# MercurialSDR_PWR.net
KiCad netlist of a schematic drawn in Altium Designer
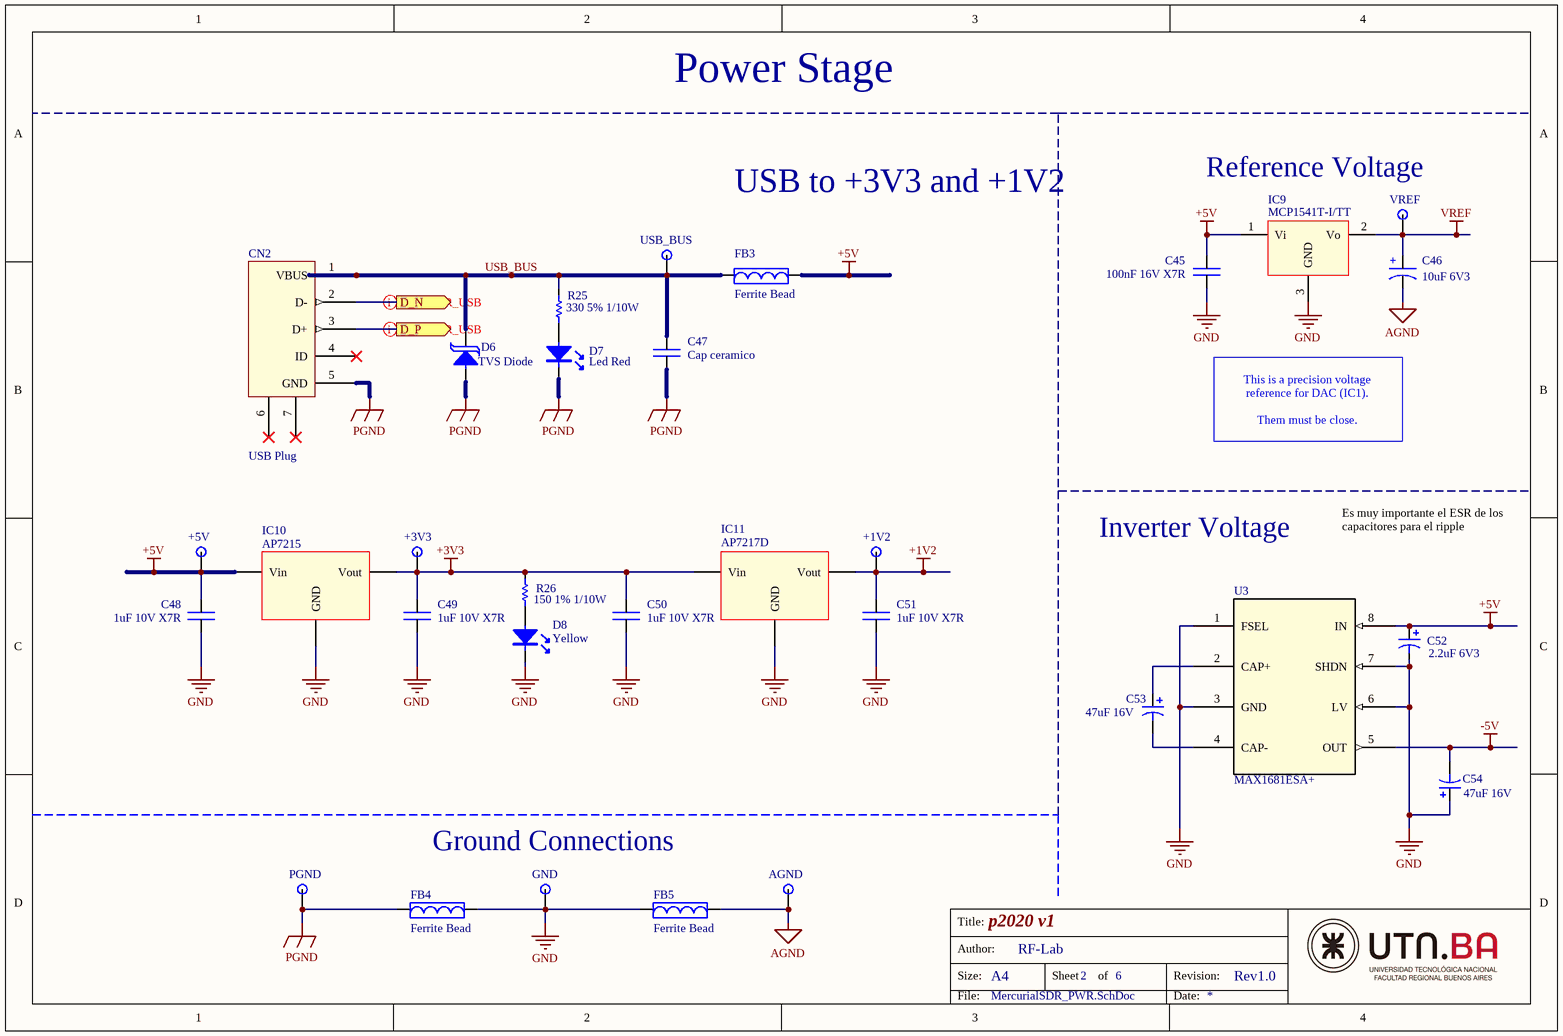
[diagram p0: MercurialSDR_PWR.SchDoc]

(export (version "E")
  (design (tool "Eeschema 10.0.6"))
  (components
    (comp (ref "C45")
      (value "100nF 16V X7R")
      (footprint "CAP_0603")
      (description "Capacitor no polarizado")
      (fields (field (name "Comment") "100nF 16V X7R - CL10B104KO8NNNC"))
      (libsource (lib "MercurialSDR") (part "Cap"))
    )
    (comp (ref "C46")
      (value "10uF 6V3")
      (footprint "CAP_TANT_1206")
      (description "Capacitor polarizado")
      (fields (field (name "Comment") "10uF 6V3 - TAJA106K006RNJ"))
      (libsource (lib "MercurialSDR") (part "Cap Pol"))
    )
    (comp (ref "C47")
      (value "Cap ceramico")
      (footprint "CAP_0603")
      (description "Capacitor no polarizado")
      (fields (field (name "Comment") "10nF 16v X7R  - CC0603KRX7R7BB103"))
      (libsource (lib "MercurialSDR") (part "Cap"))
    )
    (comp (ref "C48")
      (value "1uF 10V X7R")
      (footprint "CAP_0603")
      (description "Capacitor no polarizado")
      (fields (field (name "Comment") "1uF 10V X7R - CL10B105KP8NNNC"))
      (libsource (lib "MercurialSDR") (part "Cap"))
    )
    (comp (ref "C49")
      (value "1uF 10V X7R")
      (footprint "CAP_0603")
      (description "Capacitor no polarizado")
      (fields (field (name "Comment") "1uF 10V X7R - CL10B105KP8NNNC"))
      (libsource (lib "MercurialSDR") (part "Cap"))
    )
    (comp (ref "C50")
      (value "1uF 10V X7R")
      (footprint "CAP_0603")
      (description "Capacitor no polarizado")
      (fields (field (name "Comment") "1uF 10V X7R - CL10B105KP8NNNC"))
      (libsource (lib "MercurialSDR") (part "Cap"))
    )
    (comp (ref "C51")
      (value "1uF 10V X7R")
      (footprint "CAP_0603")
      (description "Capacitor no polarizado")
      (fields (field (name "Comment") "1uF 10V X7R - CL10B105KP8NNNC"))
      (libsource (lib "MercurialSDR") (part "Cap"))
    )
    (comp (ref "C52")
      (value "2.2uF 6V3")
      (footprint "CAP_0603")
      (description "Capacitor Polarizado")
      (fields
        (field (name "Comment") "2.2uF 6V3 -  TMCJ1A225MTRF")
        (field (name "PUBLISHER") "Altium Limited")
      )
      (libsource (lib "Miscellaneous Devices") (part "Cap Pol1"))
    )
    (comp (ref "C53")
      (value "47uF 16V")
      (footprint "CAPPC5932X280N")
      (description "Capacitor Polarizado")
      (fields
        (field (name "Comment") "47uF 16V - 595D476X9016C2T")
        (field (name "PUBLISHER") "Altium Limited")
      )
      (libsource (lib "Miscellaneous Devices") (part "Cap Pol1"))
    )
    (comp (ref "C54")
      (value "47uF 16V")
      (footprint "CAPPC5932X280N")
      (description "Capacitor Polarizado")
      (fields
        (field (name "Comment") "47uF 16V - 595D476X9016C2T")
        (field (name "PUBLISHER") "Altium Limited")
      )
      (libsource (lib "Miscellaneous Devices") (part "Cap Pol1"))
    )
    (comp (ref "CN2")
      (value "USB Plug")
      (footprint "54819-0589_MOL")
      (description "Mini-USB Plug")
      (fields (field (name "Comment") "54819-0589"))
      (libsource (lib "MercurialSDR") (part "USB Plug"))
    )
    (comp (ref "D6")
      (value "TVS Diode")
      (footprint "DO-214AC")
      (description "TVS Diode (Supresor de transitorios)")
      (fields (field (name "Comment") "SMAJ5.0A"))
      (libsource (lib "MercurialSDR") (part "TVS_DIODE"))
    )
    (comp (ref "D7")
      (value "LTST-C190KRKT")
      (footprint "LED_0603")
      (description "Led")
      (fields (field (name "COLOR") "Led Red"))
      (libsource (lib "MercurialSDR") (part "Led"))
    )
    (comp (ref "D8")
      (value "LTST-C190KSKT")
      (footprint "LED_0603")
      (description "Led Yellow")
      (fields (field (name "COLOR") "Yellow"))
      (libsource (lib "MercurialSDR") (part "Led"))
    )
    (comp (ref "FB3")
      (value "Ferrite Bead")
      (footprint "FERRITE_BEAD_0603")
      (fields (field (name "Comment") "BLM18AG121SN1D"))
      (libsource (lib "MercurialSDR") (part "Ferrite Bead"))
    )
    (comp (ref "FB4")
      (value "Ferrite Bead")
      (footprint "FERRITE_BEAD_0603")
      (fields (field (name "Comment") "BLM18AG121SN1D"))
      (libsource (lib "MercurialSDR") (part "Ferrite Bead"))
    )
    (comp (ref "FB5")
      (value "Ferrite Bead")
      (footprint "FERRITE_BEAD_0603")
      (fields (field (name "Comment") "BLM18AG121SN1D"))
      (libsource (lib "MercurialSDR") (part "Ferrite Bead"))
    )
    (comp (ref "IC9")
      (value "MCP1541T-I/TT")
      (footprint "SOT-23-3")
      (description "Reference Voltage")
      (fields (field (name "PART NUMBER") "MCP1541T-I/TT"))
      (libsource (lib "MercurialSDR") (part "MCP1541"))
    )
    (comp (ref "IC10")
      (value "AP7215")
      (footprint "SOT89-3L")
      (description "Linear Voltage Regulator 3v3")
      (fields (field (name "Comment") "AP7215 - AP7365-33YG-13"))
      (libsource (lib "MercurialSDR") (part "AP7215"))
    )
    (comp (ref "IC11")
      (value "AP7217D")
      (footprint "SOT89-3L")
      (description "Linear Voltage Regulator 1V2")
      (fields (field (name "Comment") "AP7217D - AP7217D-12YG-13"))
      (libsource (lib "MercurialSDR") (part "AP7217D"))
    )
    (comp (ref "R25")
      (value "330 5% 1/10W")
      (footprint "RES_0603")
      (description "Resistor")
      (fields (field (name "Comment") "330 5% 1/10W - CR0603-JW-331ELF"))
      (libsource (lib "MercurialSDR") (part "Res"))
    )
    (comp (ref "R26")
      (value "150 1% 1/10W")
      (footprint "RES_0603")
      (description "Resistor")
      (fields (field (name "Comment") "150 1% 1/10W - CR0603-FX-1500ELF"))
      (libsource (lib "MercurialSDR") (part "Res"))
    )
    (comp (ref "TP6")
      (value "Test Point")
      (footprint "TP_TH")
      (fields (field (name "TP NAME") "VREF"))
      (libsource (lib "MercurialSDR") (part "Test Point"))
    )
    (comp (ref "TP7")
      (value "Test Point")
      (footprint "TP_TH")
      (fields (field (name "TP NAME") "USB_BUS"))
      (libsource (lib "MercurialSDR") (part "Test Point"))
    )
    (comp (ref "TP8")
      (value "Test Point")
      (footprint "TP_TH")
      (fields (field (name "TP NAME") "+5V"))
      (libsource (lib "MercurialSDR") (part "Test Point"))
    )
    (comp (ref "TP9")
      (value "Test Point")
      (footprint "TP_TH")
      (fields (field (name "TP NAME") "+3V3"))
      (libsource (lib "MercurialSDR") (part "Test Point"))
    )
    (comp (ref "TP10")
      (value "Test Point")
      (footprint "TP_TH")
      (fields (field (name "TP NAME") "+1V2"))
      (libsource (lib "MercurialSDR") (part "Test Point"))
    )
    (comp (ref "TP11")
      (value "Test Point")
      (footprint "TP_TH")
      (fields (field (name "TP NAME") "PGND"))
      (libsource (lib "MercurialSDR") (part "Test Point"))
    )
    (comp (ref "TP12")
      (value "Test Point")
      (footprint "TP_TH")
      (fields (field (name "TP NAME") "GND"))
      (libsource (lib "MercurialSDR") (part "Test Point"))
    )
    (comp (ref "TP13")
      (value "Test Point")
      (footprint "TP_TH")
      (fields (field (name "TP NAME") "AGND"))
      (libsource (lib "MercurialSDR") (part "Test Point"))
    )
    (comp (ref "U3")
      (value "MAX1681ESA+")
      (footprint "max1681")
      (description "Voltage converter")
      (fields (field (name "COPYRIGHT") "Copyright (C) 2018 Accelerated Designs. All rights reserved"))
      (libsource (lib "MercurialSDR") (part "MAX1681"))
    )
  )
  (nets
    (net (code "1") (name "+1V2") (class "Default")
      (node (ref "C51") (pin "1") (pinfunction "1_1") (pintype "passive"))
      (node (ref "IC11") (pin "3") (pinfunction "Vout_3") (pintype "passive"))
      (node (ref "TP10") (pin "1") (pinfunction "TP?_1") (pintype "passive"))
    )
    (net (code "2") (name "+3V3") (class "Default")
      (node (ref "C49") (pin "1") (pinfunction "1_1") (pintype "passive"))
      (node (ref "C50") (pin "1") (pinfunction "1_1") (pintype "passive"))
      (node (ref "IC10") (pin "1") (pinfunction "Vout_1") (pintype "passive"))
      (node (ref "IC11") (pin "2") (pinfunction "Vin_2") (pintype "passive"))
      (node (ref "R26") (pin "1") (pinfunction "1_1") (pintype "passive"))
      (node (ref "TP9") (pin "1") (pinfunction "TP?_1") (pintype "passive"))
    )
    (net (code "3") (name "+5V") (class "Default")
      (node (ref "C45") (pin "1") (pinfunction "1_1") (pintype "passive"))
      (node (ref "C48") (pin "1") (pinfunction "1_1") (pintype "passive"))
      (node (ref "C52") (pin "1") (pinfunction "1_1") (pintype "passive"))
      (node (ref "FB3") (pin "2") (pinfunction "2_2") (pintype "passive"))
      (node (ref "IC10") (pin "3") (pinfunction "Vin_3") (pintype "passive"))
      (node (ref "IC9") (pin "1") (pinfunction "Vi_1") (pintype "passive"))
      (node (ref "TP8") (pin "1") (pinfunction "TP?_1") (pintype "passive"))
      (node (ref "U3") (pin "8") (pinfunction "IN_8") (pintype "input"))
    )
    (net (code "4") (name "-5V") (class "Default")
      (node (ref "C54") (pin "2") (pinfunction "2_2") (pintype "passive"))
      (node (ref "U3") (pin "5") (pinfunction "OUT_5") (pintype "output"))
    )
    (net (code "5") (name "/D_N") (class "Default")
      (node (ref "CN2") (pin "2") (pinfunction "D-_2") (pintype "output"))
    )
    (net (code "6") (name "/D_P") (class "Default")
      (node (ref "CN2") (pin "3") (pinfunction "D+_3") (pintype "output"))
    )
    (net (code "7") (name "/USB_BUS") (class "Default")
      (node (ref "C47") (pin "1") (pinfunction "1_1") (pintype "passive"))
      (node (ref "CN2") (pin "1") (pinfunction "VBUS_1") (pintype "power_in"))
      (node (ref "D6") (pin "2") (pinfunction "K_2") (pintype "passive"))
      (node (ref "FB3") (pin "1") (pinfunction "1_1") (pintype "passive"))
      (node (ref "R25") (pin "1") (pinfunction "1_1") (pintype "passive"))
      (node (ref "TP7") (pin "1") (pinfunction "TP?_1") (pintype "passive"))
    )
    (net (code "8") (name "AGND") (class "Default")
      (node (ref "C46") (pin "2") (pinfunction "2_2") (pintype "passive"))
      (node (ref "FB5") (pin "2") (pinfunction "2_2") (pintype "passive"))
      (node (ref "TP13") (pin "1") (pinfunction "TP?_1") (pintype "passive"))
    )
    (net (code "9") (name "GND") (class "Default")
      (node (ref "C45") (pin "2") (pinfunction "2_2") (pintype "passive"))
      (node (ref "C48") (pin "2") (pinfunction "2_2") (pintype "passive"))
      (node (ref "C49") (pin "2") (pinfunction "2_2") (pintype "passive"))
      (node (ref "C50") (pin "2") (pinfunction "2_2") (pintype "passive"))
      (node (ref "C51") (pin "2") (pinfunction "2_2") (pintype "passive"))
      (node (ref "C52") (pin "2") (pinfunction "2_2") (pintype "passive"))
      (node (ref "C54") (pin "1") (pinfunction "1_1") (pintype "passive"))
      (node (ref "D8") (pin "2") (pinfunction "K_2") (pintype "passive"))
      (node (ref "FB4") (pin "2") (pinfunction "2_2") (pintype "passive"))
      (node (ref "FB5") (pin "1") (pinfunction "1_1") (pintype "passive"))
      (node (ref "IC10") (pin "2") (pinfunction "GND_2") (pintype "passive"))
      (node (ref "IC11") (pin "1") (pinfunction "GND_1") (pintype "passive"))
      (node (ref "IC9") (pin "3") (pinfunction "GND_3") (pintype "passive"))
      (node (ref "TP12") (pin "1") (pinfunction "TP?_1") (pintype "passive"))
      (node (ref "U3") (pin "1") (pinfunction "FSEL_1") (pintype "passive"))
      (node (ref "U3") (pin "3") (pinfunction "GND_3") (pintype "power_in"))
      (node (ref "U3") (pin "6") (pinfunction "LV_6") (pintype "input"))
      (node (ref "U3") (pin "7") (pinfunction "SHDN_7") (pintype "input"))
    )
    (net (code "10") (name "Net-(D7-A)") (class "Default")
      (node (ref "D7") (pin "1") (pinfunction "A_1") (pintype "passive"))
      (node (ref "R25") (pin "2") (pinfunction "2_2") (pintype "passive"))
    )
    (net (code "11") (name "Net-(D8-A)") (class "Default")
      (node (ref "D8") (pin "1") (pinfunction "A_1") (pintype "passive"))
      (node (ref "R26") (pin "2") (pinfunction "2_2") (pintype "passive"))
    )
    (net (code "12") (name "Net-(U3-CAP+)") (class "Default")
      (node (ref "C53") (pin "1") (pinfunction "1_1") (pintype "passive"))
      (node (ref "U3") (pin "2") (pinfunction "CAP+_2") (pintype "passive"))
    )
    (net (code "13") (name "Net-(U3-CAP-)") (class "Default")
      (node (ref "C53") (pin "2") (pinfunction "2_2") (pintype "passive"))
      (node (ref "U3") (pin "4") (pinfunction "CAP-_4") (pintype "passive"))
    )
    (net (code "14") (name "PGND") (class "Default")
      (node (ref "C47") (pin "2") (pinfunction "2_2") (pintype "passive"))
      (node (ref "CN2") (pin "5") (pinfunction "GND_5") (pintype "power_in"))
      (node (ref "D6") (pin "1") (pinfunction "A_1") (pintype "passive"))
      (node (ref "D7") (pin "2") (pinfunction "K_2") (pintype "passive"))
      (node (ref "FB4") (pin "1") (pinfunction "1_1") (pintype "passive"))
      (node (ref "TP11") (pin "1") (pinfunction "TP?_1") (pintype "passive"))
    )
    (net (code "15") (name "VREF") (class "Default")
      (node (ref "C46") (pin "1") (pinfunction "1_1") (pintype "passive"))
      (node (ref "IC9") (pin "2") (pinfunction "Vo_2") (pintype "passive"))
      (node (ref "TP6") (pin "1") (pinfunction "TP?_1") (pintype "passive"))
    )
    (net (code "16") (name "unconnected-(CN2-ID-Pad4)") (class "Default")
      (node (ref "CN2") (pin "4") (pinfunction "ID_4") (pintype "power_in+no_connect"))
    )
    (net (code "17") (name "unconnected-(CN2-Shield-Pad6)") (class "Default")
      (node (ref "CN2") (pin "6") (pinfunction "Shield_6") (pintype "passive+no_connect"))
    )
    (net (code "18") (name "unconnected-(CN2-Shield-Pad7)") (class "Default")
      (node (ref "CN2") (pin "7") (pinfunction "Shield_7") (pintype "passive+no_connect"))
    )
  )
)
